# CORE.net
KiCad netlist of a schematic drawn in Altium Designer
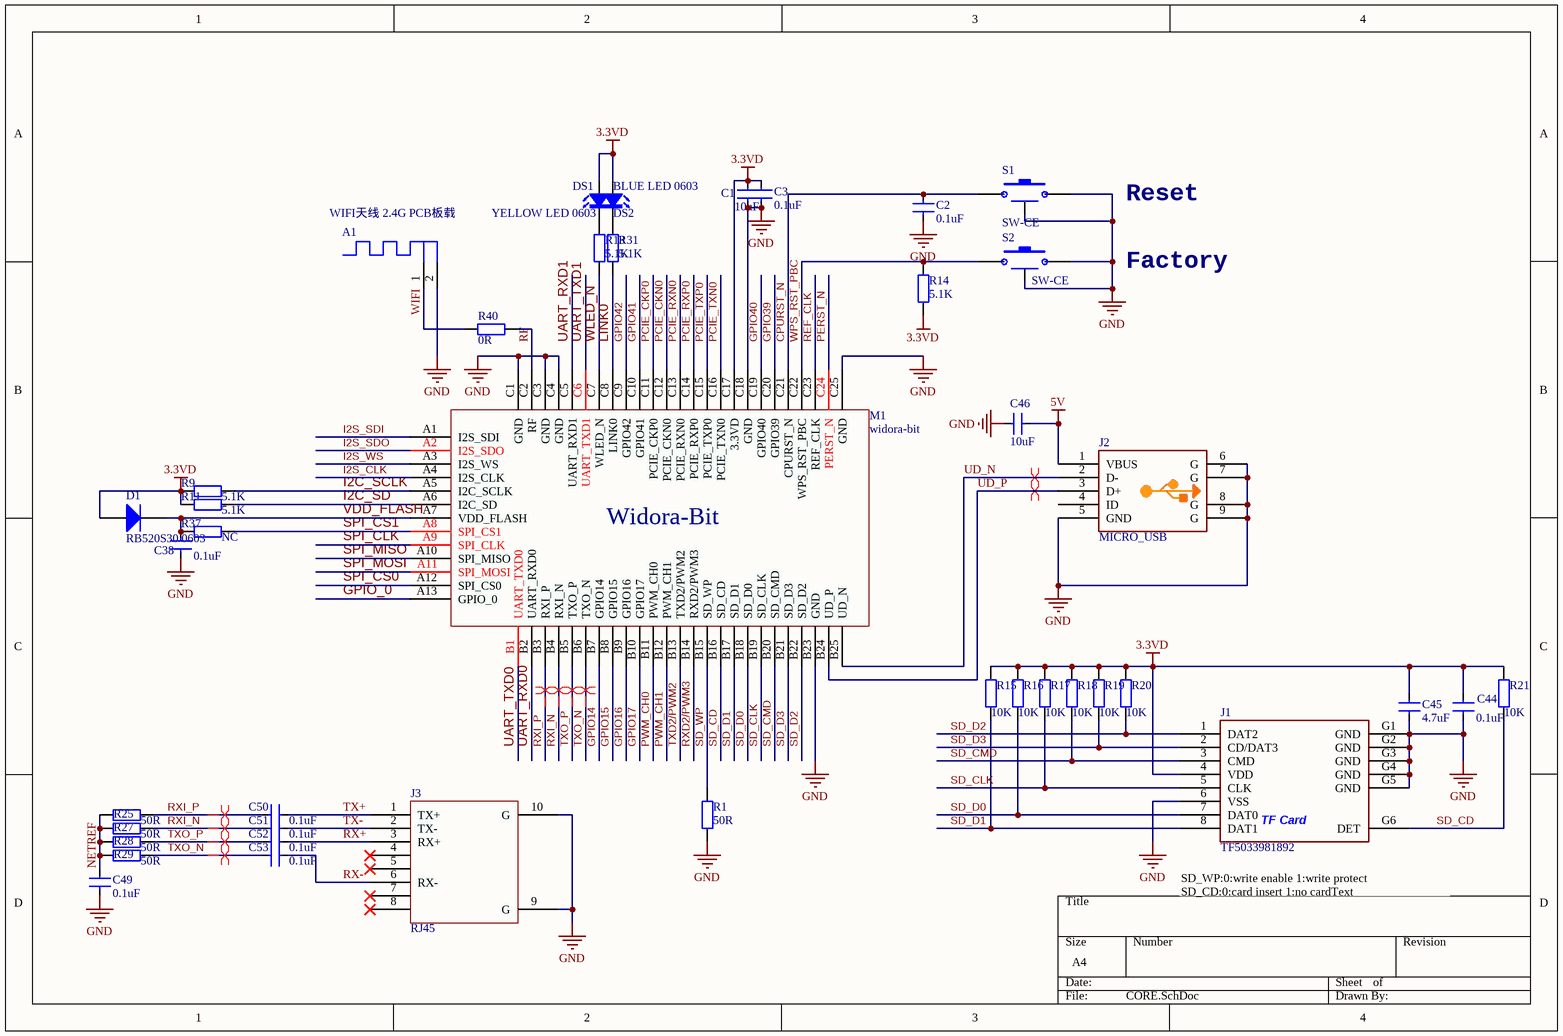
[diagram p0: CORE.SchDoc]

(export (version "E")
  (design (tool "Eeschema 10.0.6"))
  (components
    (comp (ref "A1")
      (value "WIFI天线 2.4G PCB板载")
      (footprint "2.4G - mirror")
      (libsource (lib "LIB_MANGO") (part "ANT2.4G"))
    )
    (comp (ref "C1")
      (value "10uF")
      (footprint "0805C")
      (description "普通小电容")
      (libsource (lib "LIB_MANGO") (part "CAP"))
    )
    (comp (ref "C2")
      (value "0.1uF")
      (footprint "C0402")
      (description "普通小电容")
      (libsource (lib "LIB_MANGO") (part "CAP"))
    )
    (comp (ref "C3")
      (value "0.1uF")
      (footprint "C0402")
      (description "普通小电容")
      (libsource (lib "LIB_MANGO") (part "CAP"))
    )
    (comp (ref "C38")
      (value "0.1uF")
      (footprint "C0402")
      (description "普通小电容")
      (libsource (lib "LIB_MANGO") (part "CAP"))
    )
    (comp (ref "C44")
      (value "0.1uF")
      (footprint "C0402")
      (description "普通小电容")
      (libsource (lib "LIB_MANGO") (part "CAP"))
    )
    (comp (ref "C45")
      (value "4.7uF")
      (footprint "C0402")
      (description "普通小电容")
      (libsource (lib "LIB_MANGO") (part "CAP"))
    )
    (comp (ref "C46")
      (value "10uF")
      (footprint "0805C")
      (description "普通小电容")
      (libsource (lib "LIB_MANGO") (part "CAP"))
    )
    (comp (ref "C49")
      (value "0.1uF")
      (footprint "C0402")
      (description "普通小电容")
      (libsource (lib "LIB_MANGO") (part "CAP"))
    )
    (comp (ref "C50")
      (value "0.1uF")
      (footprint "C0402")
      (description "普通小电容")
      (libsource (lib "LIB_MANGO") (part "CAP"))
    )
    (comp (ref "C51")
      (value "0.1uF")
      (footprint "C0402")
      (description "普通小电容")
      (libsource (lib "LIB_MANGO") (part "CAP"))
    )
    (comp (ref "C52")
      (value "0.1uF")
      (footprint "C0402")
      (description "普通小电容")
      (libsource (lib "LIB_MANGO") (part "CAP"))
    )
    (comp (ref "C53")
      (value "0.1uF")
      (footprint "C0402")
      (description "普通小电容")
      (libsource (lib "LIB_MANGO") (part "CAP"))
    )
    (comp (ref "D1")
      (value "RB520S30 0603")
      (footprint "SOD523")
      (description "普通二极管")
      (libsource (lib "ALL") (part "Diode"))
    )
    (comp (ref "DS1")
      (value "YELLOW LED 0603")
      (footprint "LED0603")
      (description "黄色0603发光二极管")
      (libsource (lib "") (part "LED_1"))
    )
    (comp (ref "DS2")
      (value "BLUE LED 0603")
      (footprint "LED0603")
      (description "蓝色0603发光二极管")
      (libsource (lib "LIB_MANGO") (part "LED"))
    )
    (comp (ref "J1")
      (value "TF5033981892")
      (footprint "TFCARD")
      (description "Molex TF 卡座")
      (libsource (lib "LIB_MANGO") (part "TF5033981892"))
    )
    (comp (ref "J2")
      (value "MICRO_USB")
      (footprint "MICROUSB")
      (libsource (lib "LIB_MANGO") (part "MICRO_USB"))
    )
    (comp (ref "J3")
      (value "RJ45")
      (footprint "RJ45")
      (description "RJ45不带网络变压器")
      (libsource (lib "LIB_MANGO") (part "RJ45"))
    )
    (comp (ref "M1")
      (value "widora-bit")
      (footprint "widora-core")
      (libsource (lib "LIB_MANGO") (part "widora-bit"))
    )
    (comp (ref "R1")
      (value "50R")
      (footprint "R0402")
      (description "普通电阻")
      (libsource (lib "LIB_MANGO") (part "RES"))
    )
    (comp (ref "R9")
      (value "5.1K")
      (footprint "R0402")
      (description "普通电阻")
      (libsource (lib "") (part "RES_1"))
    )
    (comp (ref "R11")
      (value "5.1K")
      (footprint "R0402")
      (description "普通电阻")
      (libsource (lib "") (part "RES_1"))
    )
    (comp (ref "R13")
      (value "5.1K")
      (footprint "R0402")
      (description "普通电阻")
      (libsource (lib "LIB_MANGO") (part "RES"))
    )
    (comp (ref "R14")
      (value "5.1K")
      (footprint "R0402")
      (description "普通电阻")
      (libsource (lib "") (part "RES_2"))
    )
    (comp (ref "R15")
      (value "10K")
      (footprint "R0402")
      (description "普通电阻")
      (libsource (lib "LIB_MANGO") (part "RES"))
    )
    (comp (ref "R16")
      (value "10K")
      (footprint "R0402")
      (description "普通电阻")
      (libsource (lib "LIB_MANGO") (part "RES"))
    )
    (comp (ref "R17")
      (value "10K")
      (footprint "R0402")
      (description "普通电阻")
      (libsource (lib "LIB_MANGO") (part "RES"))
    )
    (comp (ref "R18")
      (value "10K")
      (footprint "R0402")
      (description "普通电阻")
      (libsource (lib "LIB_MANGO") (part "RES"))
    )
    (comp (ref "R19")
      (value "10K")
      (footprint "R0402")
      (description "普通电阻")
      (libsource (lib "LIB_MANGO") (part "RES"))
    )
    (comp (ref "R20")
      (value "10K")
      (footprint "R0402")
      (description "普通电阻")
      (libsource (lib "LIB_MANGO") (part "RES"))
    )
    (comp (ref "R21")
      (value "10K")
      (footprint "R0402")
      (description "普通电阻")
      (libsource (lib "LIB_MANGO") (part "RES"))
    )
    (comp (ref "R25")
      (value "50R")
      (footprint "R0402")
      (description "普通电阻")
      (libsource (lib "") (part "RES_1"))
    )
    (comp (ref "R27")
      (value "50R")
      (footprint "R0402")
      (description "普通电阻")
      (libsource (lib "") (part "RES_1"))
    )
    (comp (ref "R28")
      (value "50R")
      (footprint "R0402")
      (description "普通电阻")
      (libsource (lib "") (part "RES_1"))
    )
    (comp (ref "R29")
      (value "50R")
      (footprint "R0402")
      (description "普通电阻")
      (libsource (lib "") (part "RES_1"))
    )
    (comp (ref "R31")
      (value "5.1K")
      (footprint "R0402")
      (description "普通电阻")
      (libsource (lib "LIB_MANGO") (part "RES"))
    )
    (comp (ref "R37")
      (value "NC")
      (footprint "R0402")
      (description "普通电阻")
      (libsource (lib "") (part "RES_3"))
    )
    (comp (ref "R40")
      (value "0R")
      (footprint "R0402")
      (description "普通电阻")
      (libsource (lib "LIB_MANGO") (part "RES"))
    )
    (comp (ref "S1") (value "SW-CE") (footprint "KEY-A06") (libsource (lib "A") (part "SW-CE")))
    (comp (ref "S2") (value "SW-CE") (footprint "KEY-A06") (libsource (lib "A") (part "SW-CE")))
  )
  (nets
    (net (code "1") (name "/CPURST_N") (class "Default")
      (node (ref "C2") (pin "2") (pinfunction "2_2") (pintype "passive"))
      (node (ref "M1") (pin "C21") (pinfunction "CPURST_N_C21") (pintype "passive"))
      (node (ref "S1") (pin "1") (pinfunction "1_1") (pintype "passive"))
    )
    (net (code "2") (name "/GPIO14") (class "Default")
      (node (ref "M1") (pin "B7") (pinfunction "GPIO14_B7") (pintype "passive"))
    )
    (net (code "3") (name "/GPIO15") (class "Default")
      (node (ref "M1") (pin "B8") (pinfunction "GPIO15_B8") (pintype "passive"))
    )
    (net (code "4") (name "/GPIO16") (class "Default")
      (node (ref "M1") (pin "B9") (pinfunction "GPIO16_B9") (pintype "passive"))
    )
    (net (code "5") (name "/GPIO17") (class "Default")
      (node (ref "M1") (pin "B10") (pinfunction "GPIO17_B10") (pintype "passive"))
    )
    (net (code "6") (name "/GPIO39") (class "Default")
      (node (ref "M1") (pin "C20") (pinfunction "GPIO39_C20") (pintype "passive"))
    )
    (net (code "7") (name "/GPIO40") (class "Default")
      (node (ref "M1") (pin "C19") (pinfunction "GPIO40_C19") (pintype "passive"))
    )
    (net (code "8") (name "/GPIO41") (class "Default")
      (node (ref "M1") (pin "C10") (pinfunction "GPIO41_C10") (pintype "passive"))
    )
    (net (code "9") (name "/GPIO42") (class "Default")
      (node (ref "M1") (pin "C9") (pinfunction "GPIO42_C9") (pintype "passive"))
    )
    (net (code "10") (name "/GPIO_0") (class "Default")
      (node (ref "M1") (pin "A13") (pinfunction "GPIO_0_A13") (pintype "passive"))
    )
    (net (code "11") (name "/I2C_SCLK") (class "Default")
      (node (ref "M1") (pin "A5") (pinfunction "I2C_SCLK_A5") (pintype "passive"))
      (node (ref "R9") (pin "1") (pinfunction "1_1") (pintype "passive"))
    )
    (net (code "12") (name "/I2C_SD") (class "Default")
      (node (ref "M1") (pin "A6") (pinfunction "I2C_SD_A6") (pintype "passive"))
      (node (ref "R11") (pin "1") (pinfunction "1_1") (pintype "passive"))
    )
    (net (code "13") (name "/I2S_CLK") (class "Default")
      (node (ref "M1") (pin "A4") (pinfunction "I2S_CLK_A4") (pintype "passive"))
    )
    (net (code "14") (name "/I2S_SDI") (class "Default")
      (node (ref "M1") (pin "A1") (pinfunction "I2S_SDI_A1") (pintype "passive"))
    )
    (net (code "15") (name "/I2S_SDO") (class "Default")
      (node (ref "M1") (pin "A2") (pinfunction "I2S_SDO_A2") (pintype "passive"))
    )
    (net (code "16") (name "/I2S_WS") (class "Default")
      (node (ref "M1") (pin "A3") (pinfunction "I2S_WS_A3") (pintype "passive"))
    )
    (net (code "17") (name "/LINK0") (class "Default")
      (node (ref "M1") (pin "C8") (pinfunction "LINK0_C8") (pintype "passive"))
      (node (ref "R31") (pin "2") (pinfunction "2_2") (pintype "passive"))
    )
    (net (code "18") (name "/NETREF") (class "Default")
      (node (ref "C49") (pin "2") (pinfunction "2_2") (pintype "passive"))
      (node (ref "R25") (pin "2") (pinfunction "2_2") (pintype "passive"))
      (node (ref "R27") (pin "2") (pinfunction "2_2") (pintype "passive"))
      (node (ref "R28") (pin "2") (pinfunction "2_2") (pintype "passive"))
      (node (ref "R29") (pin "2") (pinfunction "2_2") (pintype "passive"))
    )
    (net (code "19") (name "/PCIE_CKN0") (class "Default")
      (node (ref "M1") (pin "C12") (pinfunction "PCIE_CKN0_C12") (pintype "passive"))
    )
    (net (code "20") (name "/PCIE_CKP0") (class "Default")
      (node (ref "M1") (pin "C11") (pinfunction "PCIE_CKP0_C11") (pintype "passive"))
    )
    (net (code "21") (name "/PCIE_RXN0") (class "Default")
      (node (ref "M1") (pin "C13") (pinfunction "PCIE_RXN0_C13") (pintype "passive"))
    )
    (net (code "22") (name "/PCIE_RXP0") (class "Default")
      (node (ref "M1") (pin "C14") (pinfunction "PCIE_RXP0_C14") (pintype "passive"))
    )
    (net (code "23") (name "/PCIE_TXN0") (class "Default")
      (node (ref "M1") (pin "C16") (pinfunction "PCIE_TXN0_C16") (pintype "passive"))
    )
    (net (code "24") (name "/PCIE_TXP0") (class "Default")
      (node (ref "M1") (pin "C15") (pinfunction "PCIE_TXP0_C15") (pintype "passive"))
    )
    (net (code "25") (name "/PERST_N") (class "Default")
      (node (ref "M1") (pin "C24") (pinfunction "PERST_N_C24") (pintype "passive"))
    )
    (net (code "26") (name "/PWM_CH0") (class "Default")
      (node (ref "M1") (pin "B11") (pinfunction "PWM_CH0_B11") (pintype "passive"))
    )
    (net (code "27") (name "/PWM_CH1") (class "Default")
      (node (ref "M1") (pin "B12") (pinfunction "PWM_CH1_B12") (pintype "passive"))
    )
    (net (code "28") (name "/REF_CLK") (class "Default")
      (node (ref "M1") (pin "C23") (pinfunction "REF_CLK_C23") (pintype "passive"))
    )
    (net (code "29") (name "/RF") (class "Default")
      (node (ref "M1") (pin "C2") (pinfunction "RF_C2") (pintype "passive"))
      (node (ref "R40") (pin "1") (pinfunction "1_1") (pintype "passive"))
    )
    (net (code "30") (name "/RX+") (class "Default")
      (node (ref "C52") (pin "2") (pinfunction "2_2") (pintype "passive"))
      (node (ref "J3") (pin "3") (pinfunction "RX+_3") (pintype "power_in"))
    )
    (net (code "31") (name "/RX-") (class "Default")
      (node (ref "C53") (pin "2") (pinfunction "2_2") (pintype "passive"))
      (node (ref "J3") (pin "6") (pinfunction "RX-_6") (pintype "power_in"))
    )
    (net (code "32") (name "/RXD2{slash}PWM3") (class "Default")
      (node (ref "M1") (pin "B14") (pinfunction "RXD2/PWM3_B14") (pintype "passive"))
    )
    (net (code "33") (name "/RXI_N") (class "Default")
      (node (ref "C51") (pin "1") (pinfunction "1_1") (pintype "passive"))
      (node (ref "M1") (pin "B4") (pinfunction "RXI_N_B4") (pintype "passive"))
      (node (ref "R27") (pin "1") (pinfunction "1_1") (pintype "passive"))
    )
    (net (code "34") (name "/RXI_P") (class "Default")
      (node (ref "C50") (pin "1") (pinfunction "1_1") (pintype "passive"))
      (node (ref "M1") (pin "B3") (pinfunction "RXI_P_B3") (pintype "passive"))
      (node (ref "R25") (pin "1") (pinfunction "1_1") (pintype "passive"))
    )
    (net (code "35") (name "/SD_CD") (class "Default")
      (node (ref "J1") (pin "G6") (pinfunction "DET_G6") (pintype "power_in"))
      (node (ref "M1") (pin "B16") (pinfunction "SD_CD_B16") (pintype "passive"))
      (node (ref "R21") (pin "2") (pinfunction "2_2") (pintype "passive"))
    )
    (net (code "36") (name "/SD_CLK") (class "Default")
      (node (ref "J1") (pin "5") (pinfunction "CLK_5") (pintype "passive"))
      (node (ref "M1") (pin "B19") (pinfunction "SD_CLK_B19") (pintype "passive"))
      (node (ref "R17") (pin "2") (pinfunction "2_2") (pintype "passive"))
    )
    (net (code "37") (name "/SD_CMD") (class "Default")
      (node (ref "J1") (pin "3") (pinfunction "CMD_3") (pintype "passive"))
      (node (ref "M1") (pin "B20") (pinfunction "SD_CMD_B20") (pintype "passive"))
      (node (ref "R18") (pin "2") (pinfunction "2_2") (pintype "passive"))
    )
    (net (code "38") (name "/SD_D0") (class "Default")
      (node (ref "J1") (pin "7") (pinfunction "DAT0_7") (pintype "passive"))
      (node (ref "M1") (pin "B18") (pinfunction "SD_D0_B18") (pintype "passive"))
      (node (ref "R16") (pin "2") (pinfunction "2_2") (pintype "passive"))
    )
    (net (code "39") (name "/SD_D1") (class "Default")
      (node (ref "J1") (pin "8") (pinfunction "DAT1_8") (pintype "passive"))
      (node (ref "M1") (pin "B17") (pinfunction "SD_D1_B17") (pintype "passive"))
      (node (ref "R15") (pin "2") (pinfunction "2_2") (pintype "passive"))
    )
    (net (code "40") (name "/SD_D2") (class "Default")
      (node (ref "J1") (pin "1") (pinfunction "DAT2_1") (pintype "passive"))
      (node (ref "M1") (pin "B22") (pinfunction "SD_D2_B22") (pintype "passive"))
      (node (ref "R20") (pin "2") (pinfunction "2_2") (pintype "passive"))
    )
    (net (code "41") (name "/SD_D3") (class "Default")
      (node (ref "J1") (pin "2") (pinfunction "CD/DAT3_2") (pintype "passive"))
      (node (ref "M1") (pin "B21") (pinfunction "SD_D3_B21") (pintype "passive"))
      (node (ref "R19") (pin "2") (pinfunction "2_2") (pintype "passive"))
    )
    (net (code "42") (name "/SD_WP") (class "Default")
      (node (ref "M1") (pin "B15") (pinfunction "SD_WP_B15") (pintype "passive"))
      (node (ref "R1") (pin "1") (pinfunction "1_1") (pintype "passive"))
    )
    (net (code "43") (name "/SPI_CLK") (class "Default")
      (node (ref "M1") (pin "A9") (pinfunction "SPI_CLK_A9") (pintype "passive"))
    )
    (net (code "44") (name "/SPI_CS0") (class "Default")
      (node (ref "M1") (pin "A12") (pinfunction "SPI_CS0_A12") (pintype "passive"))
    )
    (net (code "45") (name "/SPI_CS1") (class "Default")
      (node (ref "M1") (pin "A8") (pinfunction "SPI_CS1_A8") (pintype "passive"))
      (node (ref "R37") (pin "2") (pinfunction "2_2") (pintype "passive"))
    )
    (net (code "46") (name "/SPI_MISO") (class "Default")
      (node (ref "M1") (pin "A10") (pinfunction "SPI_MISO_A10") (pintype "passive"))
    )
    (net (code "47") (name "/SPI_MOSI") (class "Default")
      (node (ref "M1") (pin "A11") (pinfunction "SPI_MOSI_A11") (pintype "passive"))
    )
    (net (code "48") (name "/TX+") (class "Default")
      (node (ref "C50") (pin "2") (pinfunction "2_2") (pintype "passive"))
      (node (ref "J3") (pin "1") (pinfunction "TX+_1") (pintype "power_in"))
    )
    (net (code "49") (name "/TX-") (class "Default")
      (node (ref "C51") (pin "2") (pinfunction "2_2") (pintype "passive"))
      (node (ref "J3") (pin "2") (pinfunction "TX-_2") (pintype "power_in"))
    )
    (net (code "50") (name "/TXD2{slash}PWM2") (class "Default")
      (node (ref "M1") (pin "B13") (pinfunction "TXD2/PWM2_B13") (pintype "passive"))
    )
    (net (code "51") (name "/TXO_N") (class "Default")
      (node (ref "C53") (pin "1") (pinfunction "1_1") (pintype "passive"))
      (node (ref "M1") (pin "B6") (pinfunction "TXO_N_B6") (pintype "passive"))
      (node (ref "R29") (pin "1") (pinfunction "1_1") (pintype "passive"))
    )
    (net (code "52") (name "/TXO_P") (class "Default")
      (node (ref "C52") (pin "1") (pinfunction "1_1") (pintype "passive"))
      (node (ref "M1") (pin "B5") (pinfunction "TXO_P_B5") (pintype "passive"))
      (node (ref "R28") (pin "1") (pinfunction "1_1") (pintype "passive"))
    )
    (net (code "53") (name "/UART_RXD0") (class "Default")
      (node (ref "M1") (pin "B2") (pinfunction "UART_RXD0_B2") (pintype "passive"))
    )
    (net (code "54") (name "/UART_RXD1") (class "Default")
      (node (ref "M1") (pin "C5") (pinfunction "UART_RXD1_C5") (pintype "passive"))
    )
    (net (code "55") (name "/UART_TXD0") (class "Default")
      (node (ref "M1") (pin "B1") (pinfunction "UART_TXD0_B1") (pintype "passive"))
    )
    (net (code "56") (name "/UART_TXD1") (class "Default")
      (node (ref "M1") (pin "C6") (pinfunction "UART_TXD1_C6") (pintype "passive"))
    )
    (net (code "57") (name "/UD_N") (class "Default")
      (node (ref "J2") (pin "2") (pinfunction "D-_2") (pintype "passive"))
      (node (ref "M1") (pin "B25") (pinfunction "UD_N_B25") (pintype "passive"))
    )
    (net (code "58") (name "/UD_P") (class "Default")
      (node (ref "J2") (pin "3") (pinfunction "D+_3") (pintype "passive"))
      (node (ref "M1") (pin "B24") (pinfunction "UD_P_B24") (pintype "passive"))
    )
    (net (code "59") (name "/VDD_FLASH") (class "Default")
      (node (ref "C38") (pin "2") (pinfunction "2_2") (pintype "passive"))
      (node (ref "D1") (pin "K") (pinfunction "K_K") (pintype "passive"))
      (node (ref "M1") (pin "A7") (pinfunction "VDD_FLASH_A7") (pintype "passive"))
      (node (ref "R37") (pin "1") (pinfunction "1_1") (pintype "passive"))
    )
    (net (code "60") (name "/WIFI") (class "Default")
      (node (ref "A1") (pin "1") (pintype "passive"))
      (node (ref "R40") (pin "2") (pinfunction "2_2") (pintype "passive"))
    )
    (net (code "61") (name "/WLED_N") (class "Default")
      (node (ref "M1") (pin "C7") (pinfunction "WLED_N_C7") (pintype "passive"))
      (node (ref "R13") (pin "2") (pinfunction "2_2") (pintype "passive"))
    )
    (net (code "62") (name "/WPS_RST_PBC") (class "Default")
      (node (ref "M1") (pin "C22") (pinfunction "WPS_RST_PBC_C22") (pintype "passive"))
      (node (ref "R14") (pin "2") (pinfunction "2_2") (pintype "passive"))
      (node (ref "S2") (pin "2") (pinfunction "2_2") (pintype "passive"))
    )
    (net (code "63") (name "3.3VD") (class "Default")
      (node (ref "C1") (pin "2") (pinfunction "2_2") (pintype "passive"))
      (node (ref "C3") (pin "2") (pinfunction "2_2") (pintype "passive"))
      (node (ref "C44") (pin "1") (pinfunction "1_1") (pintype "passive"))
      (node (ref "C45") (pin "1") (pinfunction "1_1") (pintype "passive"))
      (node (ref "D1") (pin "A") (pinfunction "A_A") (pintype "passive"))
      (node (ref "DS1") (pin "A") (pinfunction "1_A") (pintype "passive"))
      (node (ref "DS2") (pin "A") (pinfunction "1_A") (pintype "passive"))
      (node (ref "J1") (pin "4") (pinfunction "VDD_4") (pintype "power_in"))
      (node (ref "M1") (pin "C17") (pinfunction "3.3VD_C17") (pintype "passive"))
      (node (ref "R11") (pin "2") (pinfunction "2_2") (pintype "passive"))
      (node (ref "R14") (pin "1") (pinfunction "1_1") (pintype "passive"))
      (node (ref "R15") (pin "1") (pinfunction "1_1") (pintype "passive"))
      (node (ref "R16") (pin "1") (pinfunction "1_1") (pintype "passive"))
      (node (ref "R17") (pin "1") (pinfunction "1_1") (pintype "passive"))
      (node (ref "R18") (pin "1") (pinfunction "1_1") (pintype "passive"))
      (node (ref "R19") (pin "1") (pinfunction "1_1") (pintype "passive"))
      (node (ref "R20") (pin "1") (pinfunction "1_1") (pintype "passive"))
      (node (ref "R21") (pin "1") (pinfunction "1_1") (pintype "passive"))
      (node (ref "R9") (pin "2") (pinfunction "2_2") (pintype "passive"))
    )
    (net (code "64") (name "5V") (class "Default")
      (node (ref "C46") (pin "1") (pinfunction "1_1") (pintype "passive"))
      (node (ref "J2") (pin "1") (pinfunction "VBUS_1") (pintype "power_in"))
    )
    (net (code "65") (name "GND") (class "Default")
      (node (ref "A1") (pin "2") (pinfunction "G_2") (pintype "passive"))
      (node (ref "C1") (pin "1") (pinfunction "1_1") (pintype "passive"))
      (node (ref "C2") (pin "1") (pinfunction "1_1") (pintype "passive"))
      (node (ref "C3") (pin "1") (pinfunction "1_1") (pintype "passive"))
      (node (ref "C38") (pin "1") (pinfunction "1_1") (pintype "passive"))
      (node (ref "C44") (pin "2") (pinfunction "2_2") (pintype "passive"))
      (node (ref "C45") (pin "2") (pinfunction "2_2") (pintype "passive"))
      (node (ref "C46") (pin "2") (pinfunction "2_2") (pintype "passive"))
      (node (ref "C49") (pin "1") (pinfunction "1_1") (pintype "passive"))
      (node (ref "J1") (pin "6") (pinfunction "VSS_6") (pintype "power_in"))
      (node (ref "J1") (pin "G1") (pinfunction "GND_G1") (pintype "power_in"))
      (node (ref "J1") (pin "G2") (pinfunction "GND_G2") (pintype "power_in"))
      (node (ref "J1") (pin "G3") (pinfunction "GND_G3") (pintype "power_in"))
      (node (ref "J1") (pin "G4") (pinfunction "GND_G4") (pintype "power_in"))
      (node (ref "J1") (pin "G5") (pinfunction "GND_G5") (pintype "power_in"))
      (node (ref "J2") (pin "5") (pinfunction "GND_5") (pintype "power_in"))
      (node (ref "J2") (pin "6") (pinfunction "G_6") (pintype "passive"))
      (node (ref "J2") (pin "7") (pinfunction "G_7") (pintype "passive"))
      (node (ref "J2") (pin "8") (pinfunction "G_8") (pintype "passive"))
      (node (ref "J2") (pin "9") (pinfunction "G_9") (pintype "passive"))
      (node (ref "J3") (pin "10") (pinfunction "G_10") (pintype "power_in"))
      (node (ref "J3") (pin "9") (pinfunction "G_9") (pintype "power_in"))
      (node (ref "M1") (pin "B23") (pinfunction "GND_B23") (pintype "passive"))
      (node (ref "M1") (pin "C1") (pinfunction "GND_C1") (pintype "passive"))
      (node (ref "M1") (pin "C18") (pinfunction "GND_C18") (pintype "passive"))
      (node (ref "M1") (pin "C25") (pinfunction "GND_C25") (pintype "passive"))
      (node (ref "M1") (pin "C3") (pinfunction "GND_C3") (pintype "passive"))
      (node (ref "M1") (pin "C4") (pinfunction "GND_C4") (pintype "passive"))
      (node (ref "R1") (pin "2") (pinfunction "2_2") (pintype "passive"))
      (node (ref "S1") (pin "0") (pinfunction "0_0") (pintype "power_in"))
      (node (ref "S1") (pin "2") (pinfunction "2_2") (pintype "passive"))
      (node (ref "S2") (pin "0") (pinfunction "0_0") (pintype "power_in"))
      (node (ref "S2") (pin "1") (pinfunction "1_1") (pintype "passive"))
    )
    (net (code "66") (name "Net-(DS1-2)") (class "Default")
      (node (ref "DS1") (pin "K") (pinfunction "2_K") (pintype "passive"))
      (node (ref "R13") (pin "1") (pinfunction "1_1") (pintype "passive"))
    )
    (net (code "67") (name "Net-(DS2-2)") (class "Default")
      (node (ref "DS2") (pin "K") (pinfunction "2_K") (pintype "passive"))
      (node (ref "R31") (pin "1") (pinfunction "1_1") (pintype "passive"))
    )
    (net (code "68") (name "unconnected-(J2-ID-Pad4)") (class "Default")
      (node (ref "J2") (pin "4") (pinfunction "ID_4") (pintype "passive"))
    )
    (net (code "69") (name "unconnected-(J3-Pad4)") (class "Default")
      (node (ref "J3") (pin "4") (pintype "power_in+no_connect"))
    )
    (net (code "70") (name "unconnected-(J3-Pad5)") (class "Default")
      (node (ref "J3") (pin "5") (pintype "power_in+no_connect"))
    )
    (net (code "71") (name "unconnected-(J3-Pad7)") (class "Default")
      (node (ref "J3") (pin "7") (pintype "power_in+no_connect"))
    )
    (net (code "72") (name "unconnected-(J3-Pad8)") (class "Default")
      (node (ref "J3") (pin "8") (pintype "power_in+no_connect"))
    )
  )
)
